# p128necontrol.net
KiCad netlist of a schematic drawn in EAGLE
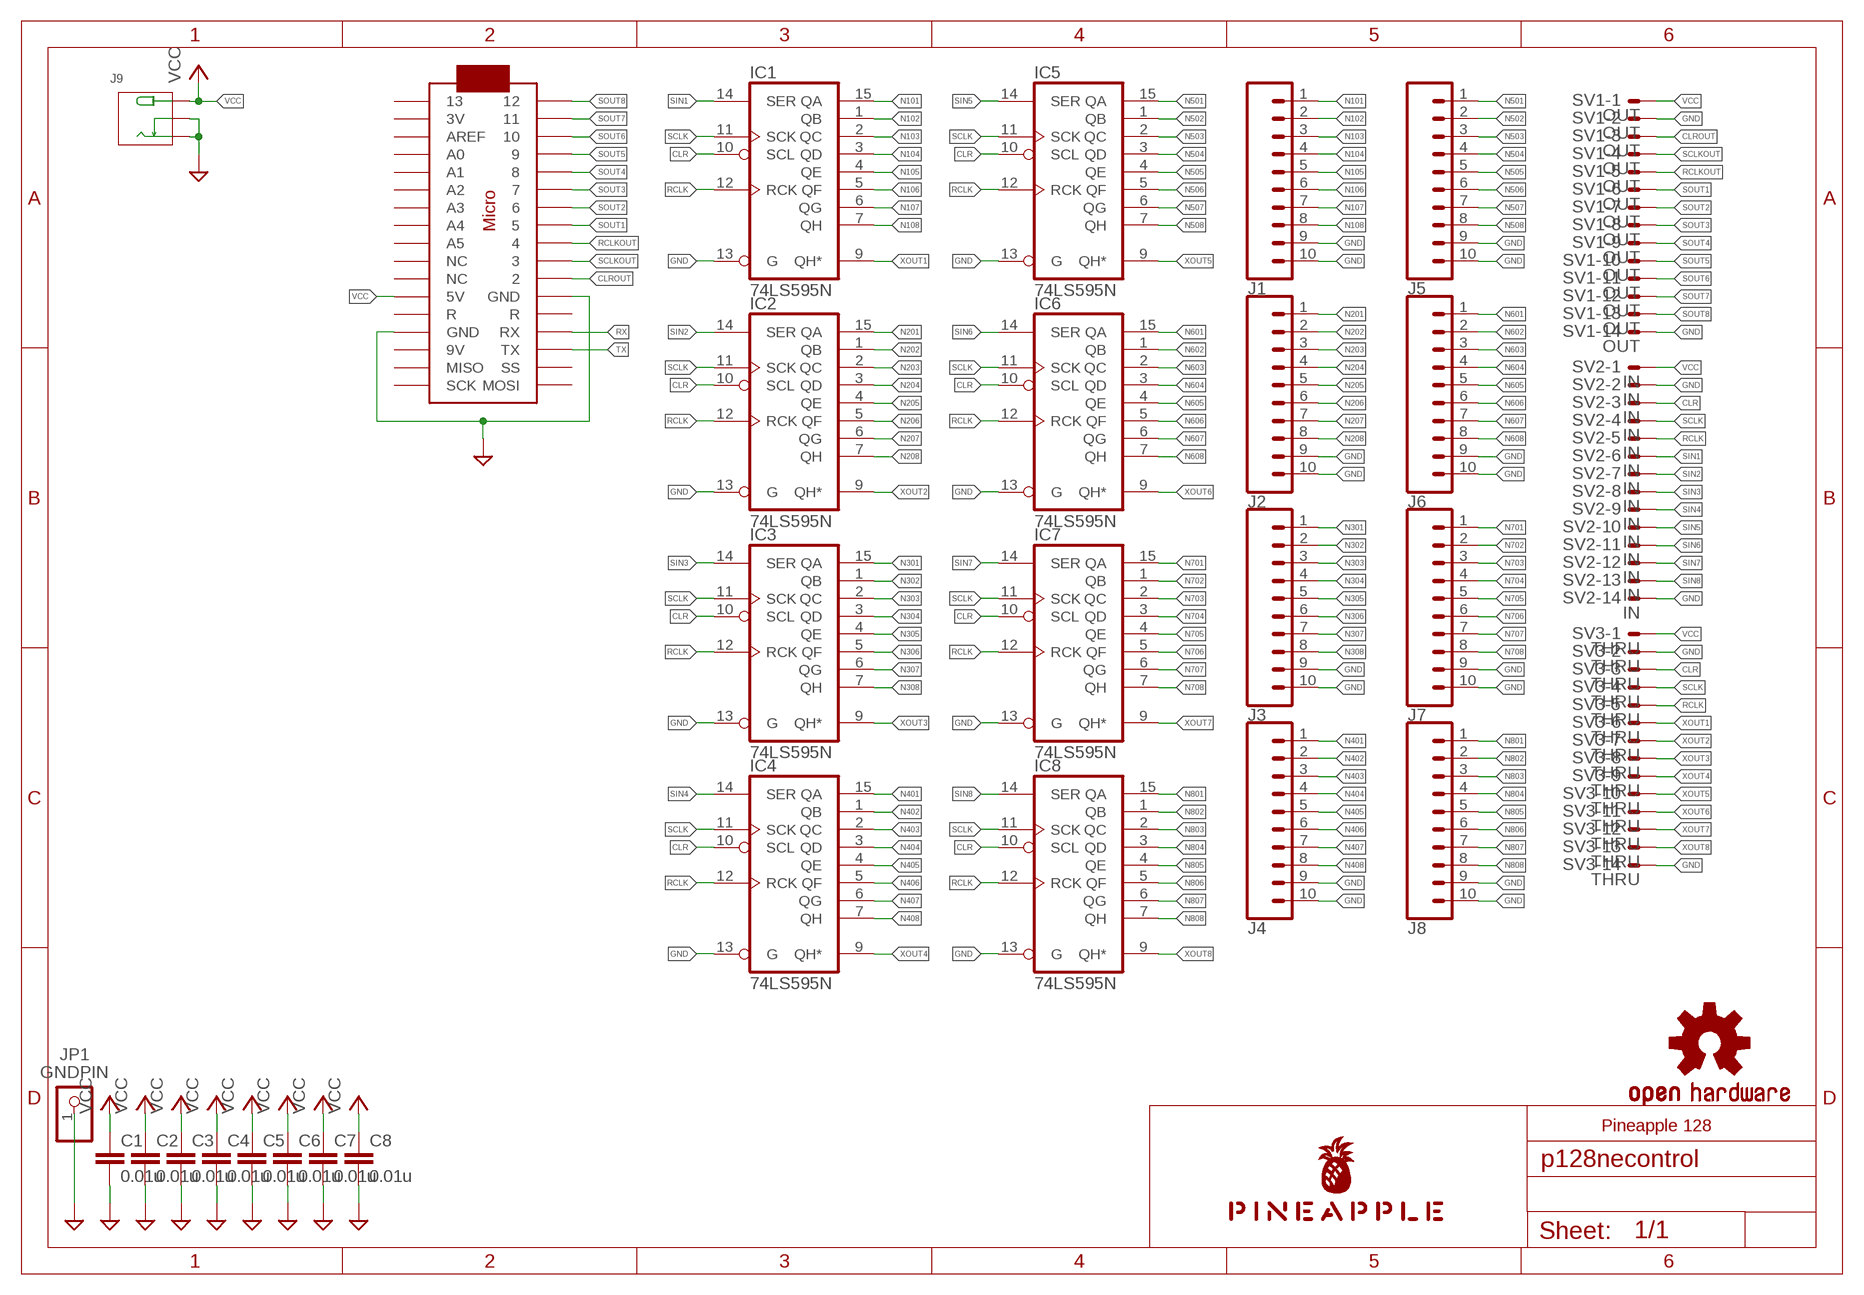
[diagram p0: schematic, sheet 1]

(export (version "E")
  (design (tool "Eeschema 10.0.6"))
  (components
    (comp (ref "C1")
      (value "0.01u")
      (footprint "eagle-import:C025-024X044")
      (libsource (lib "eagle-import") (part "C-EU025-024X044"))
    )
    (comp (ref "C2")
      (value "0.01u")
      (footprint "eagle-import:C025-024X044")
      (libsource (lib "eagle-import") (part "C-EU025-024X044"))
    )
    (comp (ref "C3")
      (value "0.01u")
      (footprint "eagle-import:C025-024X044")
      (libsource (lib "eagle-import") (part "C-EU025-024X044"))
    )
    (comp (ref "C4")
      (value "0.01u")
      (footprint "eagle-import:C025-024X044")
      (libsource (lib "eagle-import") (part "C-EU025-024X044"))
    )
    (comp (ref "C5")
      (value "0.01u")
      (footprint "eagle-import:C025-024X044")
      (libsource (lib "eagle-import") (part "C-EU025-024X044"))
    )
    (comp (ref "C6")
      (value "0.01u")
      (footprint "eagle-import:C025-024X044")
      (libsource (lib "eagle-import") (part "C-EU025-024X044"))
    )
    (comp (ref "C7")
      (value "0.01u")
      (footprint "eagle-import:C025-024X044")
      (libsource (lib "eagle-import") (part "C-EU025-024X044"))
    )
    (comp (ref "C8")
      (value "0.01u")
      (footprint "eagle-import:C025-024X044")
      (libsource (lib "eagle-import") (part "C-EU025-024X044"))
    )
    (comp (ref "IC1")
      (value "74LS595N")
      (footprint "eagle-import:DIL16")
      (libsource (lib "eagle-import") (part "74595NLS"))
    )
    (comp (ref "IC2")
      (value "74LS595N")
      (footprint "eagle-import:DIL16")
      (libsource (lib "eagle-import") (part "74595NLS"))
    )
    (comp (ref "IC3")
      (value "74LS595N")
      (footprint "eagle-import:DIL16")
      (libsource (lib "eagle-import") (part "74595NLS"))
    )
    (comp (ref "IC4")
      (value "74LS595N")
      (footprint "eagle-import:DIL16")
      (libsource (lib "eagle-import") (part "74595NLS"))
    )
    (comp (ref "IC5")
      (value "74LS595N")
      (footprint "eagle-import:DIL16")
      (libsource (lib "eagle-import") (part "74595NLS"))
    )
    (comp (ref "IC6")
      (value "74LS595N")
      (footprint "eagle-import:DIL16")
      (libsource (lib "eagle-import") (part "74595NLS"))
    )
    (comp (ref "IC7")
      (value "74LS595N")
      (footprint "eagle-import:DIL16")
      (libsource (lib "eagle-import") (part "74595NLS"))
    )
    (comp (ref "IC8")
      (value "74LS595N")
      (footprint "eagle-import:DIL16")
      (libsource (lib "eagle-import") (part "74595NLS"))
    )
    (comp (ref "J1")
      (value "CONN_10\"")
      (footprint "eagle-import:1X10")
      (libsource (lib "eagle-import") (part "CONN_10{dblquote}"))
    )
    (comp (ref "J2")
      (value "CONN_10\"")
      (footprint "eagle-import:1X10")
      (libsource (lib "eagle-import") (part "CONN_10{dblquote}"))
    )
    (comp (ref "J3")
      (value "CONN_10\"")
      (footprint "eagle-import:1X10")
      (libsource (lib "eagle-import") (part "CONN_10{dblquote}"))
    )
    (comp (ref "J4")
      (value "CONN_10\"")
      (footprint "eagle-import:1X10")
      (libsource (lib "eagle-import") (part "CONN_10{dblquote}"))
    )
    (comp (ref "J5")
      (value "CONN_10\"")
      (footprint "eagle-import:1X10")
      (libsource (lib "eagle-import") (part "CONN_10{dblquote}"))
    )
    (comp (ref "J6")
      (value "CONN_10\"")
      (footprint "eagle-import:1X10")
      (libsource (lib "eagle-import") (part "CONN_10{dblquote}"))
    )
    (comp (ref "J7")
      (value "CONN_10\"")
      (footprint "eagle-import:1X10")
      (libsource (lib "eagle-import") (part "CONN_10{dblquote}"))
    )
    (comp (ref "J8")
      (value "CONN_10\"")
      (footprint "eagle-import:1X10")
      (libsource (lib "eagle-import") (part "CONN_10{dblquote}"))
    )
    (comp (ref "J9")
      (value "JACK-DC-005'DC-005'")
      (footprint "eagle-import:3P-L14.2_W11.0_H9.0MM")
      (libsource (lib "eagle-import") (part "JACK-DC-005'DC-005'"))
    )
    (comp (ref "JP1")
      (value "GNDPIN")
      (footprint "eagle-import:1X01")
      (libsource (lib "eagle-import") (part "PINHD-1X1"))
    )
    (comp (ref "LOGO1")
      (value "OSHW-LOGOS-COPPER")
      (footprint "eagle-import:OSHW-LOGO-S_COPPER")
      (libsource (lib "eagle-import") (part "OSHW-LOGOS-COPPER"))
    )
    (comp (ref "SV1")
      (value "OUT")
      (footprint "eagle-import:ML14")
      (libsource (lib "eagle-import") (part "ML14E"))
    )
    (comp (ref "SV2")
      (value "IN")
      (footprint "eagle-import:ML14")
      (libsource (lib "eagle-import") (part "ML14E"))
    )
    (comp (ref "SV3")
      (value "THRU")
      (footprint "eagle-import:ML14")
      (libsource (lib "eagle-import") (part "ML14E"))
    )
    (comp (ref "U$1")
      (value "PINEAPPLE450_SILK")
      (footprint "eagle-import:PINEAPPLE450_SILK")
      (libsource (lib "eagle-import") (part "PINEAPPLE450_SILK"))
    )
    (comp (ref "U$2")
      (value "ARDUINOMICRO")
      (footprint "eagle-import:ARDUINOMICRO")
      (libsource (lib "eagle-import") (part "ARDUINOMICRO"))
    )
  )
  (nets
    (net (code "1") (name "CLR") (class "Default")
      (node (ref "IC1") (pin "10") (pinfunction "SCL_10") (pintype "input"))
      (node (ref "IC2") (pin "10") (pinfunction "SCL_10") (pintype "input"))
      (node (ref "IC3") (pin "10") (pinfunction "SCL_10") (pintype "input"))
      (node (ref "IC4") (pin "10") (pinfunction "SCL_10") (pintype "input"))
      (node (ref "IC5") (pin "10") (pinfunction "SCL_10") (pintype "input"))
      (node (ref "IC6") (pin "10") (pinfunction "SCL_10") (pintype "input"))
      (node (ref "IC7") (pin "10") (pinfunction "SCL_10") (pintype "input"))
      (node (ref "IC8") (pin "10") (pinfunction "SCL_10") (pintype "input"))
      (node (ref "SV2") (pin "3") (pinfunction "S_3") (pintype "passive"))
      (node (ref "SV3") (pin "3") (pinfunction "S_3") (pintype "passive"))
    )
    (net (code "2") (name "CLROUT") (class "Default")
      (node (ref "SV1") (pin "3") (pinfunction "S_3") (pintype "passive"))
      (node (ref "U$2") (pin "P$11") (pinfunction "2_P$11") (pintype "bidirectional"))
    )
    (net (code "3") (name "GND") (class "Default")
      (node (ref "C1") (pin "2") (pinfunction "2_2") (pintype "passive"))
      (node (ref "C2") (pin "2") (pinfunction "2_2") (pintype "passive"))
      (node (ref "C3") (pin "2") (pinfunction "2_2") (pintype "passive"))
      (node (ref "C4") (pin "2") (pinfunction "2_2") (pintype "passive"))
      (node (ref "C5") (pin "2") (pinfunction "2_2") (pintype "passive"))
      (node (ref "C6") (pin "2") (pinfunction "2_2") (pintype "passive"))
      (node (ref "C7") (pin "2") (pinfunction "2_2") (pintype "passive"))
      (node (ref "C8") (pin "2") (pinfunction "2_2") (pintype "passive"))
      (node (ref "IC1") (pin "13") (pinfunction "G_13") (pintype "input"))
      (node (ref "IC2") (pin "13") (pinfunction "G_13") (pintype "input"))
      (node (ref "IC3") (pin "13") (pinfunction "G_13") (pintype "input"))
      (node (ref "IC4") (pin "13") (pinfunction "G_13") (pintype "input"))
      (node (ref "IC5") (pin "13") (pinfunction "G_13") (pintype "input"))
      (node (ref "IC6") (pin "13") (pinfunction "G_13") (pintype "input"))
      (node (ref "IC7") (pin "13") (pinfunction "G_13") (pintype "input"))
      (node (ref "IC8") (pin "13") (pinfunction "G_13") (pintype "input"))
      (node (ref "J1") (pin "10") (pinfunction "10_10") (pintype "passive"))
      (node (ref "J1") (pin "9") (pinfunction "9_9") (pintype "passive"))
      (node (ref "J2") (pin "10") (pinfunction "10_10") (pintype "passive"))
      (node (ref "J2") (pin "9") (pinfunction "9_9") (pintype "passive"))
      (node (ref "J3") (pin "10") (pinfunction "10_10") (pintype "passive"))
      (node (ref "J3") (pin "9") (pinfunction "9_9") (pintype "passive"))
      (node (ref "J4") (pin "10") (pinfunction "10_10") (pintype "passive"))
      (node (ref "J4") (pin "9") (pinfunction "9_9") (pintype "passive"))
      (node (ref "J5") (pin "10") (pinfunction "10_10") (pintype "passive"))
      (node (ref "J5") (pin "9") (pinfunction "9_9") (pintype "passive"))
      (node (ref "J6") (pin "10") (pinfunction "10_10") (pintype "passive"))
      (node (ref "J6") (pin "9") (pinfunction "9_9") (pintype "passive"))
      (node (ref "J7") (pin "10") (pinfunction "10_10") (pintype "passive"))
      (node (ref "J7") (pin "9") (pinfunction "9_9") (pintype "passive"))
      (node (ref "J8") (pin "10") (pinfunction "10_10") (pintype "passive"))
      (node (ref "J8") (pin "9") (pinfunction "9_9") (pintype "passive"))
      (node (ref "J9") (pin "-1") (pinfunction "-_-1") (pintype "bidirectional"))
      (node (ref "J9") (pin "-2") (pinfunction "CDN_-2") (pintype "bidirectional"))
      (node (ref "JP1") (pin "1") (pinfunction "1_1") (pintype "passive"))
      (node (ref "SV1") (pin "14") (pinfunction "S_14") (pintype "passive"))
      (node (ref "SV1") (pin "2") (pinfunction "S_2") (pintype "passive"))
      (node (ref "SV2") (pin "14") (pinfunction "S_14") (pintype "passive"))
      (node (ref "SV2") (pin "2") (pinfunction "S_2") (pintype "passive"))
      (node (ref "SV3") (pin "14") (pinfunction "S_14") (pintype "passive"))
      (node (ref "SV3") (pin "2") (pinfunction "S_2") (pintype "passive"))
      (node (ref "U$2") (pin "P$12") (pinfunction "GND_P$12") (pintype "bidirectional"))
      (node (ref "U$2") (pin "P$21") (pinfunction "GND_P$21") (pintype "bidirectional"))
    )
    (net (code "4") (name "N101") (class "Default")
      (node (ref "IC1") (pin "15") (pinfunction "QA_15") (pintype "tri_state"))
      (node (ref "J1") (pin "1") (pinfunction "1_1") (pintype "passive"))
    )
    (net (code "5") (name "N102") (class "Default")
      (node (ref "IC1") (pin "1") (pinfunction "QB_1") (pintype "tri_state"))
      (node (ref "J1") (pin "2") (pinfunction "2_2") (pintype "passive"))
    )
    (net (code "6") (name "N103") (class "Default")
      (node (ref "IC1") (pin "2") (pinfunction "QC_2") (pintype "tri_state"))
      (node (ref "J1") (pin "3") (pinfunction "3_3") (pintype "passive"))
    )
    (net (code "7") (name "N104") (class "Default")
      (node (ref "IC1") (pin "3") (pinfunction "QD_3") (pintype "tri_state"))
      (node (ref "J1") (pin "4") (pinfunction "4_4") (pintype "passive"))
    )
    (net (code "8") (name "N105") (class "Default")
      (node (ref "IC1") (pin "4") (pinfunction "QE_4") (pintype "tri_state"))
      (node (ref "J1") (pin "5") (pinfunction "5_5") (pintype "passive"))
    )
    (net (code "9") (name "N106") (class "Default")
      (node (ref "IC1") (pin "5") (pinfunction "QF_5") (pintype "tri_state"))
      (node (ref "J1") (pin "6") (pinfunction "6_6") (pintype "passive"))
    )
    (net (code "10") (name "N107") (class "Default")
      (node (ref "IC1") (pin "6") (pinfunction "QG_6") (pintype "tri_state"))
      (node (ref "J1") (pin "7") (pinfunction "7_7") (pintype "passive"))
    )
    (net (code "11") (name "N108") (class "Default")
      (node (ref "IC1") (pin "7") (pinfunction "QH_7") (pintype "tri_state"))
      (node (ref "J1") (pin "8") (pinfunction "8_8") (pintype "passive"))
    )
    (net (code "12") (name "N201") (class "Default")
      (node (ref "IC2") (pin "15") (pinfunction "QA_15") (pintype "tri_state"))
      (node (ref "J2") (pin "1") (pinfunction "1_1") (pintype "passive"))
    )
    (net (code "13") (name "N202") (class "Default")
      (node (ref "IC2") (pin "1") (pinfunction "QB_1") (pintype "tri_state"))
      (node (ref "J2") (pin "2") (pinfunction "2_2") (pintype "passive"))
    )
    (net (code "14") (name "N203") (class "Default")
      (node (ref "IC2") (pin "2") (pinfunction "QC_2") (pintype "tri_state"))
      (node (ref "J2") (pin "3") (pinfunction "3_3") (pintype "passive"))
    )
    (net (code "15") (name "N204") (class "Default")
      (node (ref "IC2") (pin "3") (pinfunction "QD_3") (pintype "tri_state"))
      (node (ref "J2") (pin "4") (pinfunction "4_4") (pintype "passive"))
    )
    (net (code "16") (name "N205") (class "Default")
      (node (ref "IC2") (pin "4") (pinfunction "QE_4") (pintype "tri_state"))
      (node (ref "J2") (pin "5") (pinfunction "5_5") (pintype "passive"))
    )
    (net (code "17") (name "N206") (class "Default")
      (node (ref "IC2") (pin "5") (pinfunction "QF_5") (pintype "tri_state"))
      (node (ref "J2") (pin "6") (pinfunction "6_6") (pintype "passive"))
    )
    (net (code "18") (name "N207") (class "Default")
      (node (ref "IC2") (pin "6") (pinfunction "QG_6") (pintype "tri_state"))
      (node (ref "J2") (pin "7") (pinfunction "7_7") (pintype "passive"))
    )
    (net (code "19") (name "N208") (class "Default")
      (node (ref "IC2") (pin "7") (pinfunction "QH_7") (pintype "tri_state"))
      (node (ref "J2") (pin "8") (pinfunction "8_8") (pintype "passive"))
    )
    (net (code "20") (name "N301") (class "Default")
      (node (ref "IC3") (pin "15") (pinfunction "QA_15") (pintype "tri_state"))
      (node (ref "J3") (pin "1") (pinfunction "1_1") (pintype "passive"))
    )
    (net (code "21") (name "N302") (class "Default")
      (node (ref "IC3") (pin "1") (pinfunction "QB_1") (pintype "tri_state"))
      (node (ref "J3") (pin "2") (pinfunction "2_2") (pintype "passive"))
    )
    (net (code "22") (name "N303") (class "Default")
      (node (ref "IC3") (pin "2") (pinfunction "QC_2") (pintype "tri_state"))
      (node (ref "J3") (pin "3") (pinfunction "3_3") (pintype "passive"))
    )
    (net (code "23") (name "N304") (class "Default")
      (node (ref "IC3") (pin "3") (pinfunction "QD_3") (pintype "tri_state"))
      (node (ref "J3") (pin "4") (pinfunction "4_4") (pintype "passive"))
    )
    (net (code "24") (name "N305") (class "Default")
      (node (ref "IC3") (pin "4") (pinfunction "QE_4") (pintype "tri_state"))
      (node (ref "J3") (pin "5") (pinfunction "5_5") (pintype "passive"))
    )
    (net (code "25") (name "N306") (class "Default")
      (node (ref "IC3") (pin "5") (pinfunction "QF_5") (pintype "tri_state"))
      (node (ref "J3") (pin "6") (pinfunction "6_6") (pintype "passive"))
    )
    (net (code "26") (name "N307") (class "Default")
      (node (ref "IC3") (pin "6") (pinfunction "QG_6") (pintype "tri_state"))
      (node (ref "J3") (pin "7") (pinfunction "7_7") (pintype "passive"))
    )
    (net (code "27") (name "N308") (class "Default")
      (node (ref "IC3") (pin "7") (pinfunction "QH_7") (pintype "tri_state"))
      (node (ref "J3") (pin "8") (pinfunction "8_8") (pintype "passive"))
    )
    (net (code "28") (name "N401") (class "Default")
      (node (ref "IC4") (pin "15") (pinfunction "QA_15") (pintype "tri_state"))
      (node (ref "J4") (pin "1") (pinfunction "1_1") (pintype "passive"))
    )
    (net (code "29") (name "N402") (class "Default")
      (node (ref "IC4") (pin "1") (pinfunction "QB_1") (pintype "tri_state"))
      (node (ref "J4") (pin "2") (pinfunction "2_2") (pintype "passive"))
    )
    (net (code "30") (name "N403") (class "Default")
      (node (ref "IC4") (pin "2") (pinfunction "QC_2") (pintype "tri_state"))
      (node (ref "J4") (pin "3") (pinfunction "3_3") (pintype "passive"))
    )
    (net (code "31") (name "N404") (class "Default")
      (node (ref "IC4") (pin "3") (pinfunction "QD_3") (pintype "tri_state"))
      (node (ref "J4") (pin "4") (pinfunction "4_4") (pintype "passive"))
    )
    (net (code "32") (name "N405") (class "Default")
      (node (ref "IC4") (pin "4") (pinfunction "QE_4") (pintype "tri_state"))
      (node (ref "J4") (pin "5") (pinfunction "5_5") (pintype "passive"))
    )
    (net (code "33") (name "N406") (class "Default")
      (node (ref "IC4") (pin "5") (pinfunction "QF_5") (pintype "tri_state"))
      (node (ref "J4") (pin "6") (pinfunction "6_6") (pintype "passive"))
    )
    (net (code "34") (name "N407") (class "Default")
      (node (ref "IC4") (pin "6") (pinfunction "QG_6") (pintype "tri_state"))
      (node (ref "J4") (pin "7") (pinfunction "7_7") (pintype "passive"))
    )
    (net (code "35") (name "N408") (class "Default")
      (node (ref "IC4") (pin "7") (pinfunction "QH_7") (pintype "tri_state"))
      (node (ref "J4") (pin "8") (pinfunction "8_8") (pintype "passive"))
    )
    (net (code "36") (name "N501") (class "Default")
      (node (ref "IC5") (pin "15") (pinfunction "QA_15") (pintype "tri_state"))
      (node (ref "J5") (pin "1") (pinfunction "1_1") (pintype "passive"))
    )
    (net (code "37") (name "N502") (class "Default")
      (node (ref "IC5") (pin "1") (pinfunction "QB_1") (pintype "tri_state"))
      (node (ref "J5") (pin "2") (pinfunction "2_2") (pintype "passive"))
    )
    (net (code "38") (name "N503") (class "Default")
      (node (ref "IC5") (pin "2") (pinfunction "QC_2") (pintype "tri_state"))
      (node (ref "J5") (pin "3") (pinfunction "3_3") (pintype "passive"))
    )
    (net (code "39") (name "N504") (class "Default")
      (node (ref "IC5") (pin "3") (pinfunction "QD_3") (pintype "tri_state"))
      (node (ref "J5") (pin "4") (pinfunction "4_4") (pintype "passive"))
    )
    (net (code "40") (name "N505") (class "Default")
      (node (ref "IC5") (pin "4") (pinfunction "QE_4") (pintype "tri_state"))
      (node (ref "J5") (pin "5") (pinfunction "5_5") (pintype "passive"))
    )
    (net (code "41") (name "N506") (class "Default")
      (node (ref "IC5") (pin "5") (pinfunction "QF_5") (pintype "tri_state"))
      (node (ref "J5") (pin "6") (pinfunction "6_6") (pintype "passive"))
    )
    (net (code "42") (name "N507") (class "Default")
      (node (ref "IC5") (pin "6") (pinfunction "QG_6") (pintype "tri_state"))
      (node (ref "J5") (pin "7") (pinfunction "7_7") (pintype "passive"))
    )
    (net (code "43") (name "N508") (class "Default")
      (node (ref "IC5") (pin "7") (pinfunction "QH_7") (pintype "tri_state"))
      (node (ref "J5") (pin "8") (pinfunction "8_8") (pintype "passive"))
    )
    (net (code "44") (name "N601") (class "Default")
      (node (ref "IC6") (pin "15") (pinfunction "QA_15") (pintype "tri_state"))
      (node (ref "J6") (pin "1") (pinfunction "1_1") (pintype "passive"))
    )
    (net (code "45") (name "N602") (class "Default")
      (node (ref "IC6") (pin "1") (pinfunction "QB_1") (pintype "tri_state"))
      (node (ref "J6") (pin "2") (pinfunction "2_2") (pintype "passive"))
    )
    (net (code "46") (name "N603") (class "Default")
      (node (ref "IC6") (pin "2") (pinfunction "QC_2") (pintype "tri_state"))
      (node (ref "J6") (pin "3") (pinfunction "3_3") (pintype "passive"))
    )
    (net (code "47") (name "N604") (class "Default")
      (node (ref "IC6") (pin "3") (pinfunction "QD_3") (pintype "tri_state"))
      (node (ref "J6") (pin "4") (pinfunction "4_4") (pintype "passive"))
    )
    (net (code "48") (name "N605") (class "Default")
      (node (ref "IC6") (pin "4") (pinfunction "QE_4") (pintype "tri_state"))
      (node (ref "J6") (pin "5") (pinfunction "5_5") (pintype "passive"))
    )
    (net (code "49") (name "N606") (class "Default")
      (node (ref "IC6") (pin "5") (pinfunction "QF_5") (pintype "tri_state"))
      (node (ref "J6") (pin "6") (pinfunction "6_6") (pintype "passive"))
    )
    (net (code "50") (name "N607") (class "Default")
      (node (ref "IC6") (pin "6") (pinfunction "QG_6") (pintype "tri_state"))
      (node (ref "J6") (pin "7") (pinfunction "7_7") (pintype "passive"))
    )
    (net (code "51") (name "N608") (class "Default")
      (node (ref "IC6") (pin "7") (pinfunction "QH_7") (pintype "tri_state"))
      (node (ref "J6") (pin "8") (pinfunction "8_8") (pintype "passive"))
    )
    (net (code "52") (name "N701") (class "Default")
      (node (ref "IC7") (pin "15") (pinfunction "QA_15") (pintype "tri_state"))
      (node (ref "J7") (pin "1") (pinfunction "1_1") (pintype "passive"))
    )
    (net (code "53") (name "N702") (class "Default")
      (node (ref "IC7") (pin "1") (pinfunction "QB_1") (pintype "tri_state"))
      (node (ref "J7") (pin "2") (pinfunction "2_2") (pintype "passive"))
    )
    (net (code "54") (name "N703") (class "Default")
      (node (ref "IC7") (pin "2") (pinfunction "QC_2") (pintype "tri_state"))
      (node (ref "J7") (pin "3") (pinfunction "3_3") (pintype "passive"))
    )
    (net (code "55") (name "N704") (class "Default")
      (node (ref "IC7") (pin "3") (pinfunction "QD_3") (pintype "tri_state"))
      (node (ref "J7") (pin "4") (pinfunction "4_4") (pintype "passive"))
    )
    (net (code "56") (name "N705") (class "Default")
      (node (ref "IC7") (pin "4") (pinfunction "QE_4") (pintype "tri_state"))
      (node (ref "J7") (pin "5") (pinfunction "5_5") (pintype "passive"))
    )
    (net (code "57") (name "N706") (class "Default")
      (node (ref "IC7") (pin "5") (pinfunction "QF_5") (pintype "tri_state"))
      (node (ref "J7") (pin "6") (pinfunction "6_6") (pintype "passive"))
    )
    (net (code "58") (name "N707") (class "Default")
      (node (ref "IC7") (pin "6") (pinfunction "QG_6") (pintype "tri_state"))
      (node (ref "J7") (pin "7") (pinfunction "7_7") (pintype "passive"))
    )
    (net (code "59") (name "N708") (class "Default")
      (node (ref "IC7") (pin "7") (pinfunction "QH_7") (pintype "tri_state"))
      (node (ref "J7") (pin "8") (pinfunction "8_8") (pintype "passive"))
    )
    (net (code "60") (name "N801") (class "Default")
      (node (ref "IC8") (pin "15") (pinfunction "QA_15") (pintype "tri_state"))
      (node (ref "J8") (pin "1") (pinfunction "1_1") (pintype "passive"))
    )
    (net (code "61") (name "N802") (class "Default")
      (node (ref "IC8") (pin "1") (pinfunction "QB_1") (pintype "tri_state"))
      (node (ref "J8") (pin "2") (pinfunction "2_2") (pintype "passive"))
    )
    (net (code "62") (name "N803") (class "Default")
      (node (ref "IC8") (pin "2") (pinfunction "QC_2") (pintype "tri_state"))
      (node (ref "J8") (pin "3") (pinfunction "3_3") (pintype "passive"))
    )
    (net (code "63") (name "N804") (class "Default")
      (node (ref "IC8") (pin "3") (pinfunction "QD_3") (pintype "tri_state"))
      (node (ref "J8") (pin "4") (pinfunction "4_4") (pintype "passive"))
    )
    (net (code "64") (name "N805") (class "Default")
      (node (ref "IC8") (pin "4") (pinfunction "QE_4") (pintype "tri_state"))
      (node (ref "J8") (pin "5") (pinfunction "5_5") (pintype "passive"))
    )
    (net (code "65") (name "N806") (class "Default")
      (node (ref "IC8") (pin "5") (pinfunction "QF_5") (pintype "tri_state"))
      (node (ref "J8") (pin "6") (pinfunction "6_6") (pintype "passive"))
    )
    (net (code "66") (name "N807") (class "Default")
      (node (ref "IC8") (pin "6") (pinfunction "QG_6") (pintype "tri_state"))
      (node (ref "J8") (pin "7") (pinfunction "7_7") (pintype "passive"))
    )
    (net (code "67") (name "N808") (class "Default")
      (node (ref "IC8") (pin "7") (pinfunction "QH_7") (pintype "tri_state"))
      (node (ref "J8") (pin "8") (pinfunction "8_8") (pintype "passive"))
    )
    (net (code "68") (name "RCLK") (class "Default")
      (node (ref "IC1") (pin "12") (pinfunction "RCK_12") (pintype "input"))
      (node (ref "IC2") (pin "12") (pinfunction "RCK_12") (pintype "input"))
      (node (ref "IC3") (pin "12") (pinfunction "RCK_12") (pintype "input"))
      (node (ref "IC4") (pin "12") (pinfunction "RCK_12") (pintype "input"))
      (node (ref "IC5") (pin "12") (pinfunction "RCK_12") (pintype "input"))
      (node (ref "IC6") (pin "12") (pinfunction "RCK_12") (pintype "input"))
      (node (ref "IC7") (pin "12") (pinfunction "RCK_12") (pintype "input"))
      (node (ref "IC8") (pin "12") (pinfunction "RCK_12") (pintype "input"))
      (node (ref "SV2") (pin "5") (pinfunction "S_5") (pintype "passive"))
      (node (ref "SV3") (pin "5") (pinfunction "S_5") (pintype "passive"))
    )
    (net (code "69") (name "RCLKOUT") (class "Default")
      (node (ref "SV1") (pin "5") (pinfunction "S_5") (pintype "passive"))
      (node (ref "U$2") (pin "P$9") (pinfunction "4_P$9") (pintype "bidirectional"))
    )
    (net (code "70") (name "RX") (class "Default")
      (node (ref "U$2") (pin "P$14") (pinfunction "RX_P$14") (pintype "bidirectional"))
    )
    (net (code "71") (name "SCLK") (class "Default")
      (node (ref "IC1") (pin "11") (pinfunction "SCK_11") (pintype "input"))
      (node (ref "IC2") (pin "11") (pinfunction "SCK_11") (pintype "input"))
      (node (ref "IC3") (pin "11") (pinfunction "SCK_11") (pintype "input"))
      (node (ref "IC4") (pin "11") (pinfunction "SCK_11") (pintype "input"))
      (node (ref "IC5") (pin "11") (pinfunction "SCK_11") (pintype "input"))
      (node (ref "IC6") (pin "11") (pinfunction "SCK_11") (pintype "input"))
      (node (ref "IC7") (pin "11") (pinfunction "SCK_11") (pintype "input"))
      (node (ref "IC8") (pin "11") (pinfunction "SCK_11") (pintype "input"))
      (node (ref "SV2") (pin "4") (pinfunction "S_4") (pintype "passive"))
      (node (ref "SV3") (pin "4") (pinfunction "S_4") (pintype "passive"))
    )
    (net (code "72") (name "SCLKOUT") (class "Default")
      (node (ref "SV1") (pin "4") (pinfunction "S_4") (pintype "passive"))
      (node (ref "U$2") (pin "P$10") (pinfunction "3_P$10") (pintype "bidirectional"))
    )
    (net (code "73") (name "SIN1") (class "Default")
      (node (ref "IC1") (pin "14") (pinfunction "SER_14") (pintype "input"))
      (node (ref "SV2") (pin "6") (pinfunction "S_6") (pintype "passive"))
    )
    (net (code "74") (name "SIN2") (class "Default")
      (node (ref "IC2") (pin "14") (pinfunction "SER_14") (pintype "input"))
      (node (ref "SV2") (pin "7") (pinfunction "S_7") (pintype "passive"))
    )
    (net (code "75") (name "SIN3") (class "Default")
      (node (ref "IC3") (pin "14") (pinfunction "SER_14") (pintype "input"))
      (node (ref "SV2") (pin "8") (pinfunction "S_8") (pintype "passive"))
    )
    (net (code "76") (name "SIN4") (class "Default")
      (node (ref "IC4") (pin "14") (pinfunction "SER_14") (pintype "input"))
      (node (ref "SV2") (pin "9") (pinfunction "S_9") (pintype "passive"))
    )
    (net (code "77") (name "SIN5") (class "Default")
      (node (ref "IC5") (pin "14") (pinfunction "SER_14") (pintype "input"))
      (node (ref "SV2") (pin "10") (pinfunction "S_10") (pintype "passive"))
    )
    (net (code "78") (name "SIN6") (class "Default")
      (node (ref "IC6") (pin "14") (pinfunction "SER_14") (pintype "input"))
      (node (ref "SV2") (pin "11") (pinfunction "S_11") (pintype "passive"))
    )
    (net (code "79") (name "SIN7") (class "Default")
      (node (ref "IC7") (pin "14") (pinfunction "SER_14") (pintype "input"))
      (node (ref "SV2") (pin "12") (pinfunction "S_12") (pintype "passive"))
    )
    (net (code "80") (name "SIN8") (class "Default")
      (node (ref "IC8") (pin "14") (pinfunction "SER_14") (pintype "input"))
      (node (ref "SV2") (pin "13") (pinfunction "S_13") (pintype "passive"))
    )
    (net (code "81") (name "SOUT1") (class "Default")
      (node (ref "SV1") (pin "6") (pinfunction "S_6") (pintype "passive"))
      (node (ref "U$2") (pin "P$8") (pinfunction "5_P$8") (pintype "bidirectional"))
    )
    (net (code "82") (name "SOUT2") (class "Default")
      (node (ref "SV1") (pin "7") (pinfunction "S_7") (pintype "passive"))
      (node (ref "U$2") (pin "P$7") (pinfunction "6_P$7") (pintype "bidirectional"))
    )
    (net (code "83") (name "SOUT3") (class "Default")
      (node (ref "SV1") (pin "8") (pinfunction "S_8") (pintype "passive"))
      (node (ref "U$2") (pin "P$6") (pinfunction "7_P$6") (pintype "bidirectional"))
    )
    (net (code "84") (name "SOUT4") (class "Default")
      (node (ref "SV1") (pin "9") (pinfunction "S_9") (pintype "passive"))
      (node (ref "U$2") (pin "P$5") (pinfunction "8_P$5") (pintype "bidirectional"))
    )
    (net (code "85") (name "SOUT5") (class "Default")
      (node (ref "SV1") (pin "10") (pinfunction "S_10") (pintype "passive"))
      (node (ref "U$2") (pin "P$4") (pinfunction "9_P$4") (pintype "bidirectional"))
    )
    (net (code "86") (name "SOUT6") (class "Default")
      (node (ref "SV1") (pin "11") (pinfunction "S_11") (pintype "passive"))
      (node (ref "U$2") (pin "P$3") (pinfunction "10_P$3") (pintype "bidirectional"))
    )
    (net (code "87") (name "SOUT7") (class "Default")
      (node (ref "SV1") (pin "12") (pinfunction "S_12") (pintype "passive"))
      (node (ref "U$2") (pin "P$2") (pinfunction "11_P$2") (pintype "bidirectional"))
    )
    (net (code "88") (name "SOUT8") (class "Default")
      (node (ref "SV1") (pin "13") (pinfunction "S_13") (pintype "passive"))
      (node (ref "U$2") (pin "P$1") (pinfunction "12_P$1") (pintype "bidirectional"))
    )
    (net (code "89") (name "TX") (class "Default")
      (node (ref "U$2") (pin "P$15") (pinfunction "TX_P$15") (pintype "bidirectional"))
    )
    (net (code "90") (name "VCC") (class "Default")
      (node (ref "C1") (pin "1") (pinfunction "1_1") (pintype "passive"))
      (node (ref "C2") (pin "1") (pinfunction "1_1") (pintype "passive"))
      (node (ref "C3") (pin "1") (pinfunction "1_1") (pintype "passive"))
      (node (ref "C4") (pin "1") (pinfunction "1_1") (pintype "passive"))
      (node (ref "C5") (pin "1") (pinfunction "1_1") (pintype "passive"))
      (node (ref "C6") (pin "1") (pinfunction "1_1") (pintype "passive"))
      (node (ref "C7") (pin "1") (pinfunction "1_1") (pintype "passive"))
      (node (ref "C8") (pin "1") (pinfunction "1_1") (pintype "passive"))
      (node (ref "J9") (pin "+") (pinfunction "+_+") (pintype "bidirectional"))
      (node (ref "SV1") (pin "1") (pinfunction "S_1") (pintype "passive"))
      (node (ref "SV2") (pin "1") (pinfunction "S_1") (pintype "passive"))
      (node (ref "SV3") (pin "1") (pinfunction "S_1") (pintype "passive"))
      (node (ref "U$2") (pin "P$23") (pinfunction "5V_P$23") (pintype "bidirectional"))
    )
    (net (code "91") (name "XOUT1") (class "Default")
      (node (ref "IC1") (pin "9") (pinfunction "QH*_9") (pintype "tri_state"))
      (node (ref "SV3") (pin "6") (pinfunction "S_6") (pintype "passive"))
    )
    (net (code "92") (name "XOUT2") (class "Default")
      (node (ref "IC2") (pin "9") (pinfunction "QH*_9") (pintype "tri_state"))
      (node (ref "SV3") (pin "7") (pinfunction "S_7") (pintype "passive"))
    )
    (net (code "93") (name "XOUT3") (class "Default")
      (node (ref "IC3") (pin "9") (pinfunction "QH*_9") (pintype "tri_state"))
      (node (ref "SV3") (pin "8") (pinfunction "S_8") (pintype "passive"))
    )
    (net (code "94") (name "XOUT4") (class "Default")
      (node (ref "IC4") (pin "9") (pinfunction "QH*_9") (pintype "tri_state"))
      (node (ref "SV3") (pin "9") (pinfunction "S_9") (pintype "passive"))
    )
    (net (code "95") (name "XOUT5") (class "Default")
      (node (ref "IC5") (pin "9") (pinfunction "QH*_9") (pintype "tri_state"))
      (node (ref "SV3") (pin "10") (pinfunction "S_10") (pintype "passive"))
    )
    (net (code "96") (name "XOUT6") (class "Default")
      (node (ref "IC6") (pin "9") (pinfunction "QH*_9") (pintype "tri_state"))
      (node (ref "SV3") (pin "11") (pinfunction "S_11") (pintype "passive"))
    )
    (net (code "97") (name "XOUT7") (class "Default")
      (node (ref "IC7") (pin "9") (pinfunction "QH*_9") (pintype "tri_state"))
      (node (ref "SV3") (pin "12") (pinfunction "S_12") (pintype "passive"))
    )
    (net (code "98") (name "XOUT8") (class "Default")
      (node (ref "IC8") (pin "9") (pinfunction "QH*_9") (pintype "tri_state"))
      (node (ref "SV3") (pin "13") (pinfunction "S_13") (pintype "passive"))
    )
    (net (code "99") (name "unconnected-(U$2-3V-PadP$33)") (class "Default")
      (node (ref "U$2") (pin "P$33") (pinfunction "3V_P$33") (pintype "bidirectional"))
    )
    (net (code "100") (name "unconnected-(U$2-9V-PadP$20)") (class "Default")
      (node (ref "U$2") (pin "P$20") (pinfunction "9V_P$20") (pintype "bidirectional"))
    )
    (net (code "101") (name "unconnected-(U$2-13-PadP$34)") (class "Default")
      (node (ref "U$2") (pin "P$34") (pinfunction "13_P$34") (pintype "bidirectional"))
    )
    (net (code "102") (name "unconnected-(U$2-A0-PadP$31)") (class "Default")
      (node (ref "U$2") (pin "P$31") (pinfunction "A0_P$31") (pintype "bidirectional"))
    )
    (net (code "103") (name "unconnected-(U$2-A1-PadP$30)") (class "Default")
      (node (ref "U$2") (pin "P$30") (pinfunction "A1_P$30") (pintype "bidirectional"))
    )
    (net (code "104") (name "unconnected-(U$2-A2-PadP$29)") (class "Default")
      (node (ref "U$2") (pin "P$29") (pinfunction "A2_P$29") (pintype "bidirectional"))
    )
    (net (code "105") (name "unconnected-(U$2-A3-PadP$28)") (class "Default")
      (node (ref "U$2") (pin "P$28") (pinfunction "A3_P$28") (pintype "bidirectional"))
    )
    (net (code "106") (name "unconnected-(U$2-A4-PadP$27)") (class "Default")
      (node (ref "U$2") (pin "P$27") (pinfunction "A4_P$27") (pintype "bidirectional"))
    )
    (net (code "107") (name "unconnected-(U$2-A5-PadP$26)") (class "Default")
      (node (ref "U$2") (pin "P$26") (pinfunction "A5_P$26") (pintype "bidirectional"))
    )
    (net (code "108") (name "unconnected-(U$2-AREF-PadP$32)") (class "Default")
      (node (ref "U$2") (pin "P$32") (pinfunction "AREF_P$32") (pintype "bidirectional"))
    )
    (net (code "109") (name "unconnected-(U$2-MISO-PadP$19)") (class "Default")
      (node (ref "U$2") (pin "P$19") (pinfunction "MISO_P$19") (pintype "bidirectional"))
    )
    (net (code "110") (name "unconnected-(U$2-MOSI-PadP$17)") (class "Default")
      (node (ref "U$2") (pin "P$17") (pinfunction "MOSI_P$17") (pintype "bidirectional"))
    )
    (net (code "111") (name "unconnected-(U$2-NC-PadP$24)") (class "Default")
      (node (ref "U$2") (pin "P$24") (pinfunction "NC_P$24") (pintype "bidirectional"))
    )
    (net (code "112") (name "unconnected-(U$2-NC-PadP$25)") (class "Default")
      (node (ref "U$2") (pin "P$25") (pinfunction "NC_P$25") (pintype "bidirectional"))
    )
    (net (code "113") (name "unconnected-(U$2-R-PadP$13)") (class "Default")
      (node (ref "U$2") (pin "P$13") (pinfunction "R_P$13") (pintype "bidirectional"))
    )
    (net (code "114") (name "unconnected-(U$2-R-PadP$22)") (class "Default")
      (node (ref "U$2") (pin "P$22") (pinfunction "R_P$22") (pintype "bidirectional"))
    )
    (net (code "115") (name "unconnected-(U$2-SCK-PadP$18)") (class "Default")
      (node (ref "U$2") (pin "P$18") (pinfunction "SCK_P$18") (pintype "bidirectional"))
    )
    (net (code "116") (name "unconnected-(U$2-SS-PadP$16)") (class "Default")
      (node (ref "U$2") (pin "P$16") (pinfunction "SS_P$16") (pintype "bidirectional"))
    )
  )
)
